# communication.net
KiCad netlist of a schematic drawn in Altium Designer
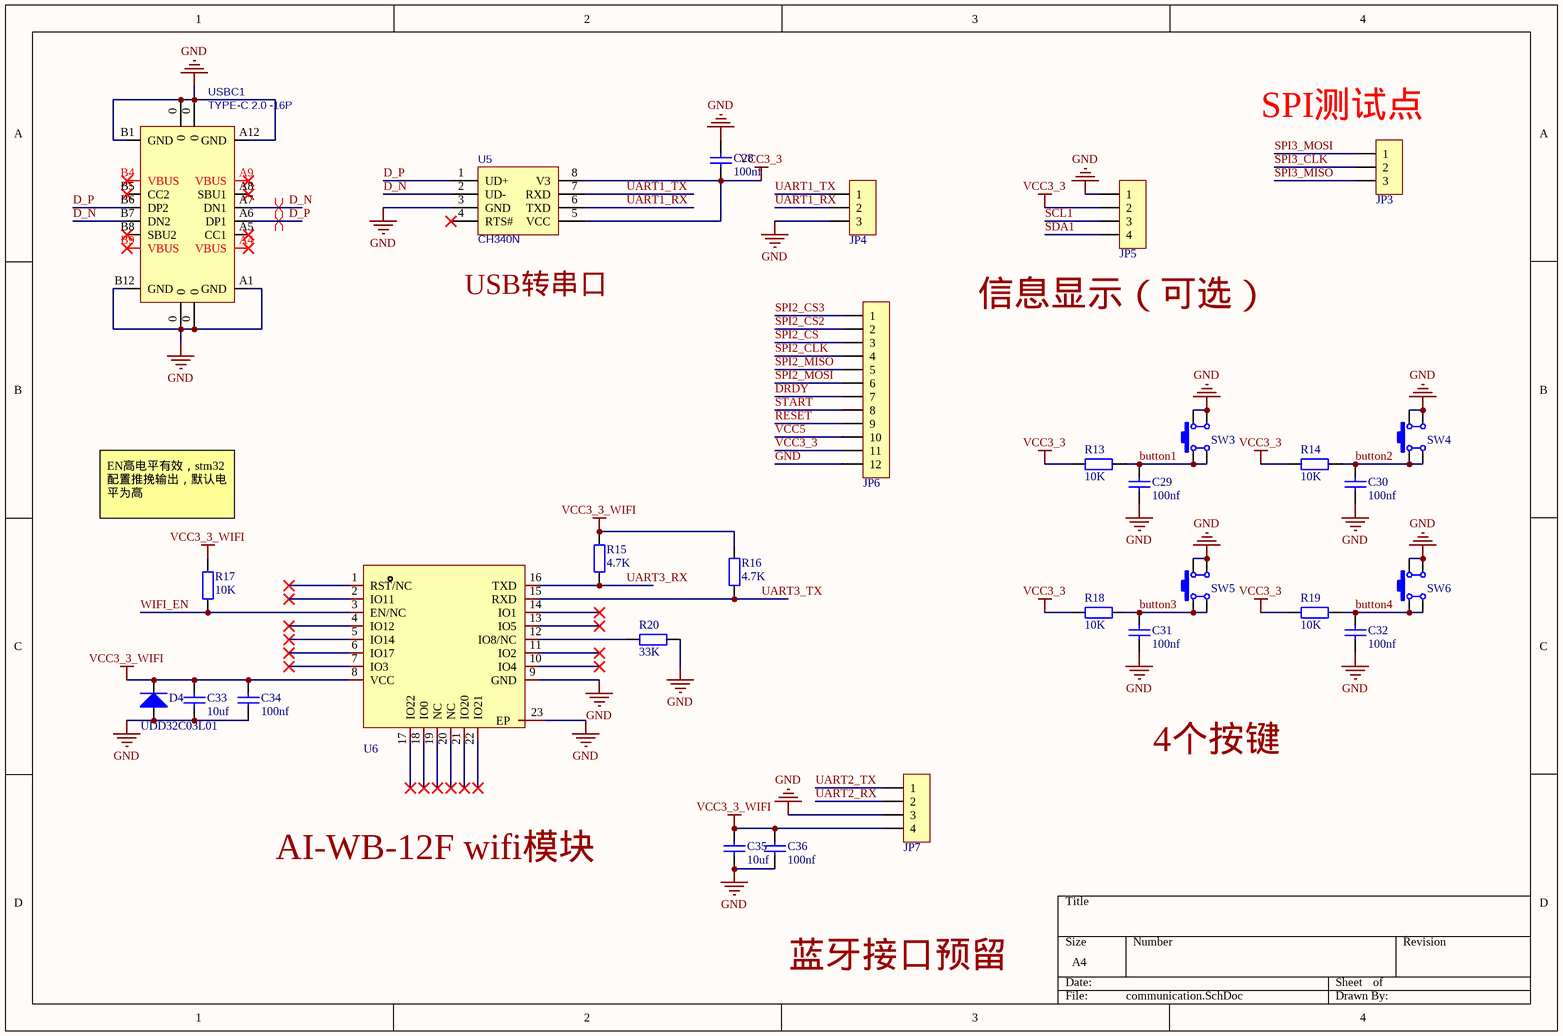
[diagram p0: communication.SchDoc]

(export (version "E")
  (design (tool "Eeschema 10.0.6"))
  (components
    (comp (ref "C28")
      (value "100nf")
      (footprint "C0603_L")
      (description "贴片电容/MLCC电容")
      (libsource (lib "0.1 - 电阻-电容-电感-保险丝-晶振-晶体-磁珠-电位器-法拉电容-馈通电容") (part "C"))
    )
    (comp (ref "C29")
      (value "100nf")
      (footprint "C0603_L")
      (description "贴片电容/MLCC电容")
      (libsource (lib "0.1 - 电阻-电容-电感-保险丝-晶振-晶体-磁珠-电位器-法拉电容-馈通电容") (part "C"))
    )
    (comp (ref "C30")
      (value "100nf")
      (footprint "C0603_L")
      (description "贴片电容/MLCC电容")
      (libsource (lib "0.1 - 电阻-电容-电感-保险丝-晶振-晶体-磁珠-电位器-法拉电容-馈通电容") (part "C"))
    )
    (comp (ref "C31")
      (value "100nf")
      (footprint "C0603_L")
      (description "贴片电容/MLCC电容")
      (libsource (lib "0.1 - 电阻-电容-电感-保险丝-晶振-晶体-磁珠-电位器-法拉电容-馈通电容") (part "C"))
    )
    (comp (ref "C32")
      (value "100nf")
      (footprint "C0603_L")
      (description "贴片电容/MLCC电容")
      (libsource (lib "0.1 - 电阻-电容-电感-保险丝-晶振-晶体-磁珠-电位器-法拉电容-馈通电容") (part "C"))
    )
    (comp (ref "C33")
      (value "10uf")
      (footprint "C0603_L")
      (description "贴片电容/MLCC电容")
      (libsource (lib "0.1 - 电阻-电容-电感-保险丝-晶振-晶体-磁珠-电位器-法拉电容-馈通电容") (part "C"))
    )
    (comp (ref "C34")
      (value "100nf")
      (footprint "C0603_L")
      (description "贴片电容/MLCC电容")
      (libsource (lib "0.1 - 电阻-电容-电感-保险丝-晶振-晶体-磁珠-电位器-法拉电容-馈通电容") (part "C"))
    )
    (comp (ref "C35")
      (value "10uf")
      (footprint "C0603_L")
      (description "贴片电容/MLCC电容")
      (libsource (lib "0.1 - 电阻-电容-电感-保险丝-晶振-晶体-磁珠-电位器-法拉电容-馈通电容") (part "C"))
    )
    (comp (ref "C36")
      (value "100nf")
      (footprint "C0603_L")
      (description "贴片电容/MLCC电容")
      (libsource (lib "0.1 - 电阻-电容-电感-保险丝-晶振-晶体-磁珠-电位器-法拉电容-馈通电容") (part "C"))
    )
    (comp (ref "D4")
      (value "UDD32C03L01")
      (footprint "SOD-323")
      (description "静电和浪涌保护 3.3V双向")
      (libsource (lib "HT") (part "UDD32C03L01"))
    )
    (comp (ref "JP3")
      (value "HDR-1X3")
      (footprint "HDR2.54-LI-3P")
      (description "3P接插件")
      (libsource (lib "5.5 - 2.54mm连接器(KF2EDGK_XH2.54_2.54排针排母)") (part "Header 3"))
    )
    (comp (ref "JP4")
      (value "HDR-1X3")
      (footprint "HDR2.54-LI-3P")
      (description "3P接插件")
      (libsource (lib "5.5 - 2.54mm连接器(KF2EDGK_XH2.54_2.54排针排母)") (part "Header 3"))
    )
    (comp (ref "JP5")
      (value "HDR-1X4")
      (footprint "HDR2.54-M-LI-4P")
      (description "4P接插件")
      (libsource (lib "5.5 - 2.54mm连接器(KF2EDGK_XH2.54_2.54排针排母)") (part "Header 4"))
    )
    (comp (ref "JP6")
      (value "HDR-1X12")
      (footprint "HDR2.54-M-LI-12P")
      (description "12P接插件")
      (libsource (lib "5.5 - 2.54mm连接器(KF2EDGK_XH2.54_2.54排针排母)") (part "Header 12"))
    )
    (comp (ref "JP7")
      (value "HDR-1X4")
      (footprint "HDR2.54-M-LI-4P")
      (description "4P接插件")
      (libsource (lib "5.5 - 2.54mm连接器(KF2EDGK_XH2.54_2.54排针排母)") (part "Header 4"))
    )
    (comp (ref "R13")
      (value "10K")
      (footprint "R0603_L")
      (description "贴片电阻")
      (libsource (lib "0.1 - 电阻-电容-电感-保险丝-晶振-晶体-磁珠-电位器-法拉电容-馈通电容") (part "R"))
    )
    (comp (ref "R14")
      (value "10K")
      (footprint "R0603_L")
      (description "贴片电阻")
      (libsource (lib "0.1 - 电阻-电容-电感-保险丝-晶振-晶体-磁珠-电位器-法拉电容-馈通电容") (part "R"))
    )
    (comp (ref "R15")
      (value "4.7K")
      (footprint "R0402_L")
      (description "贴片电阻")
      (libsource (lib "0.1 - 电阻-电容-电感-保险丝-晶振-晶体-磁珠-电位器-法拉电容-馈通电容") (part "R"))
    )
    (comp (ref "R16")
      (value "4.7K")
      (footprint "R0402_L")
      (description "贴片电阻")
      (libsource (lib "0.1 - 电阻-电容-电感-保险丝-晶振-晶体-磁珠-电位器-法拉电容-馈通电容") (part "R"))
    )
    (comp (ref "R17")
      (value "10K")
      (footprint "R0402_L")
      (description "贴片电阻")
      (libsource (lib "0.1 - 电阻-电容-电感-保险丝-晶振-晶体-磁珠-电位器-法拉电容-馈通电容") (part "R"))
    )
    (comp (ref "R18")
      (value "10K")
      (footprint "R0603_L")
      (description "贴片电阻")
      (libsource (lib "0.1 - 电阻-电容-电感-保险丝-晶振-晶体-磁珠-电位器-法拉电容-馈通电容") (part "R"))
    )
    (comp (ref "R19")
      (value "10K")
      (footprint "R0603_L")
      (description "贴片电阻")
      (libsource (lib "0.1 - 电阻-电容-电感-保险丝-晶振-晶体-磁珠-电位器-法拉电容-馈通电容") (part "R"))
    )
    (comp (ref "R20")
      (value "33K")
      (footprint "R0402_L")
      (description "贴片电阻")
      (libsource (lib "0.1 - 电阻-电容-电感-保险丝-晶振-晶体-磁珠-电位器-法拉电容-馈通电容") (part "R"))
    )
    (comp (ref "SW3")
      (value "3*4*2.5")
      (footprint "SW-SMD-4.2x3.2_4P")
      (description "贴片4脚轻触开关")
      (libsource (lib "0.5 - 按键_开关_蜂鸣器_电池_测试点_Mark点_铜柱") (part "SW SMD-3*4*2.5"))
    )
    (comp (ref "SW4")
      (value "3*4*2.5")
      (footprint "SW-SMD-4.2x3.2_4P")
      (description "贴片4脚轻触开关")
      (libsource (lib "0.5 - 按键_开关_蜂鸣器_电池_测试点_Mark点_铜柱") (part "SW SMD-3*4*2.5"))
    )
    (comp (ref "SW5")
      (value "3*4*2.5")
      (footprint "SW-SMD-4.2x3.2_4P")
      (description "贴片4脚轻触开关")
      (libsource (lib "0.5 - 按键_开关_蜂鸣器_电池_测试点_Mark点_铜柱") (part "SW SMD-3*4*2.5"))
    )
    (comp (ref "SW6")
      (value "3*4*2.5")
      (footprint "SW-SMD-4.2x3.2_4P")
      (description "贴片4脚轻触开关")
      (libsource (lib "0.5 - 按键_开关_蜂鸣器_电池_测试点_Mark点_铜柱") (part "SW SMD-3*4*2.5"))
    )
    (comp (ref "U5")
      (value "CH340N")
      (footprint "SOIC-8")
      (description "USB转串口芯片, 内置晶振")
      (libsource (lib "0.8 - 常见芯片") (part "CH340N"))
    )
    (comp (ref "U6")
      (value "Ai-WB2-12F")
      (footprint "ai-wb-12f")
      (description "esp32-12f的替代 2.4g wifi和蓝牙")
      (fields (field (name "MANUFACTURER") "Ai-Thinker(安信可)"))
      (libsource (lib "HT") (part "Ai-WB2-12F"))
    )
    (comp (ref "USBC1")
      (value "TYPE-C 2.0 -16P")
      (footprint "USB-C-SMD_16P")
      (description "USB2.0_Type-C_16Pin母座 C2765186")
      (libsource (lib "0.6 - 电源_音频_USB Type-C_HDMI_XT60_5557_D-SUB_RJ45_SD-TF_SIM插座") (part "USB2.0_Type-C_16Pin"))
    )
  )
  (nets
    (net (code "1") (name "/DRDY") (class "Default")
      (node (ref "JP6") (pin "7") (pinfunction "7_7") (pintype "passive"))
    )
    (net (code "2") (name "/D_N") (class "Default")
      (node (ref "U5") (pin "2") (pinfunction "UD-_2") (pintype "passive"))
      (node (ref "USBC1") (pin "A7") (pinfunction "DN1_A7") (pintype "passive"))
      (node (ref "USBC1") (pin "B7") (pinfunction "DN2_B7") (pintype "passive"))
    )
    (net (code "3") (name "/D_P") (class "Default")
      (node (ref "U5") (pin "1") (pinfunction "UD+_1") (pintype "passive"))
      (node (ref "USBC1") (pin "A6") (pinfunction "DP1_A6") (pintype "passive"))
      (node (ref "USBC1") (pin "B6") (pinfunction "DP2_B6") (pintype "passive"))
    )
    (net (code "4") (name "/RESET") (class "Default")
      (node (ref "JP6") (pin "9") (pinfunction "9_9") (pintype "passive"))
    )
    (net (code "5") (name "/SCL1") (class "Default")
      (node (ref "JP5") (pin "3") (pinfunction "3_3") (pintype "passive"))
    )
    (net (code "6") (name "/SDA1") (class "Default")
      (node (ref "JP5") (pin "4") (pinfunction "4_4") (pintype "passive"))
    )
    (net (code "7") (name "/SPI2_CLK") (class "Default")
      (node (ref "JP6") (pin "4") (pinfunction "4_4") (pintype "passive"))
    )
    (net (code "8") (name "/SPI2_CS") (class "Default")
      (node (ref "JP6") (pin "3") (pinfunction "3_3") (pintype "passive"))
    )
    (net (code "9") (name "/SPI2_CS2") (class "Default")
      (node (ref "JP6") (pin "2") (pinfunction "2_2") (pintype "passive"))
    )
    (net (code "10") (name "/SPI2_CS3") (class "Default")
      (node (ref "JP6") (pin "1") (pinfunction "1_1") (pintype "passive"))
    )
    (net (code "11") (name "/SPI2_MISO") (class "Default")
      (node (ref "JP6") (pin "5") (pinfunction "5_5") (pintype "passive"))
    )
    (net (code "12") (name "/SPI2_MOSI") (class "Default")
      (node (ref "JP6") (pin "6") (pinfunction "6_6") (pintype "passive"))
    )
    (net (code "13") (name "/SPI3_CLK") (class "Default")
      (node (ref "JP3") (pin "2") (pinfunction "2_2") (pintype "passive"))
    )
    (net (code "14") (name "/SPI3_MISO") (class "Default")
      (node (ref "JP3") (pin "3") (pinfunction "3_3") (pintype "passive"))
    )
    (net (code "15") (name "/SPI3_MOSI") (class "Default")
      (node (ref "JP3") (pin "1") (pinfunction "1_1") (pintype "passive"))
    )
    (net (code "16") (name "/START") (class "Default")
      (node (ref "JP6") (pin "8") (pinfunction "8_8") (pintype "passive"))
    )
    (net (code "17") (name "/UART1_RX") (class "Default")
      (node (ref "JP4") (pin "2") (pinfunction "2_2") (pintype "passive"))
      (node (ref "U5") (pin "6") (pinfunction "TXD_6") (pintype "passive"))
    )
    (net (code "18") (name "/UART1_TX") (class "Default")
      (node (ref "JP4") (pin "1") (pinfunction "1_1") (pintype "passive"))
      (node (ref "U5") (pin "7") (pinfunction "RXD_7") (pintype "passive"))
    )
    (net (code "19") (name "/UART2_RX") (class "Default")
      (node (ref "JP7") (pin "2") (pinfunction "2_2") (pintype "passive"))
    )
    (net (code "20") (name "/UART2_TX") (class "Default")
      (node (ref "JP7") (pin "1") (pinfunction "1_1") (pintype "passive"))
    )
    (net (code "21") (name "/UART3_RX") (class "Default")
      (node (ref "R15") (pin "2") (pinfunction "2_2") (pintype "passive"))
      (node (ref "U6") (pin "16") (pinfunction "TXD_16") (pintype "passive"))
    )
    (net (code "22") (name "/UART3_TX") (class "Default")
      (node (ref "R16") (pin "2") (pinfunction "2_2") (pintype "passive"))
      (node (ref "U6") (pin "15") (pinfunction "RXD_15") (pintype "passive"))
    )
    (net (code "23") (name "/VCC5") (class "Default")
      (node (ref "JP6") (pin "10") (pinfunction "10_10") (pintype "passive"))
    )
    (net (code "24") (name "/WIFI_EN") (class "Default")
      (node (ref "R17") (pin "1") (pinfunction "1_1") (pintype "passive"))
      (node (ref "U6") (pin "3") (pinfunction "EN/NC_3") (pintype "passive"))
    )
    (net (code "25") (name "/button1") (class "Default")
      (node (ref "C29") (pin "2") (pinfunction "2_2") (pintype "passive"))
      (node (ref "R13") (pin "2") (pinfunction "2_2") (pintype "passive"))
      (node (ref "SW3") (pin "1") (pinfunction "1_1") (pintype "passive"))
      (node (ref "SW3") (pin "4") (pinfunction "4_4") (pintype "passive"))
    )
    (net (code "26") (name "/button2") (class "Default")
      (node (ref "C30") (pin "2") (pinfunction "2_2") (pintype "passive"))
      (node (ref "R14") (pin "2") (pinfunction "2_2") (pintype "passive"))
      (node (ref "SW4") (pin "1") (pinfunction "1_1") (pintype "passive"))
      (node (ref "SW4") (pin "4") (pinfunction "4_4") (pintype "passive"))
    )
    (net (code "27") (name "/button3") (class "Default")
      (node (ref "C31") (pin "2") (pinfunction "2_2") (pintype "passive"))
      (node (ref "R18") (pin "2") (pinfunction "2_2") (pintype "passive"))
      (node (ref "SW5") (pin "1") (pinfunction "1_1") (pintype "passive"))
      (node (ref "SW5") (pin "4") (pinfunction "4_4") (pintype "passive"))
    )
    (net (code "28") (name "/button4") (class "Default")
      (node (ref "C32") (pin "2") (pinfunction "2_2") (pintype "passive"))
      (node (ref "R19") (pin "2") (pinfunction "2_2") (pintype "passive"))
      (node (ref "SW6") (pin "1") (pinfunction "1_1") (pintype "passive"))
      (node (ref "SW6") (pin "4") (pinfunction "4_4") (pintype "passive"))
    )
    (net (code "29") (name "GND") (class "Default")
      (node (ref "C28") (pin "2") (pinfunction "2_2") (pintype "passive"))
      (node (ref "C29") (pin "1") (pinfunction "1_1") (pintype "passive"))
      (node (ref "C30") (pin "1") (pinfunction "1_1") (pintype "passive"))
      (node (ref "C31") (pin "1") (pinfunction "1_1") (pintype "passive"))
      (node (ref "C32") (pin "1") (pinfunction "1_1") (pintype "passive"))
      (node (ref "C33") (pin "1") (pinfunction "1_1") (pintype "passive"))
      (node (ref "C34") (pin "1") (pinfunction "1_1") (pintype "passive"))
      (node (ref "C35") (pin "1") (pinfunction "1_1") (pintype "passive"))
      (node (ref "C36") (pin "1") (pinfunction "1_1") (pintype "passive"))
      (node (ref "D4") (pin "1") (pinfunction "A_1") (pintype "passive"))
      (node (ref "JP4") (pin "3") (pinfunction "3_3") (pintype "passive"))
      (node (ref "JP5") (pin "1") (pinfunction "1_1") (pintype "passive"))
      (node (ref "JP6") (pin "12") (pinfunction "12_12") (pintype "passive"))
      (node (ref "JP7") (pin "3") (pinfunction "3_3") (pintype "passive"))
      (node (ref "R20") (pin "1") (pinfunction "1_1") (pintype "passive"))
      (node (ref "SW3") (pin "2") (pinfunction "2_2") (pintype "passive"))
      (node (ref "SW3") (pin "3") (pinfunction "3_3") (pintype "passive"))
      (node (ref "SW4") (pin "2") (pinfunction "2_2") (pintype "passive"))
      (node (ref "SW4") (pin "3") (pinfunction "3_3") (pintype "passive"))
      (node (ref "SW5") (pin "2") (pinfunction "2_2") (pintype "passive"))
      (node (ref "SW5") (pin "3") (pinfunction "3_3") (pintype "passive"))
      (node (ref "SW6") (pin "2") (pinfunction "2_2") (pintype "passive"))
      (node (ref "SW6") (pin "3") (pinfunction "3_3") (pintype "passive"))
      (node (ref "U5") (pin "3") (pinfunction "GND_3") (pintype "passive"))
      (node (ref "U6") (pin "23") (pinfunction "EP_23") (pintype "passive"))
      (node (ref "U6") (pin "9") (pinfunction "GND_9") (pintype "passive"))
      (node (ref "USBC1") (pin "0") (pinfunction "0_0") (pintype "passive"))
      (node (ref "USBC1") (pin "A1") (pinfunction "GND_A1") (pintype "passive"))
      (node (ref "USBC1") (pin "A12") (pinfunction "GND_A12") (pintype "passive"))
      (node (ref "USBC1") (pin "B1") (pinfunction "GND_B1") (pintype "passive"))
      (node (ref "USBC1") (pin "B12") (pinfunction "GND_B12") (pintype "passive"))
    )
    (net (code "30") (name "Net-(U6-IO8{slash}NC)") (class "Default")
      (node (ref "R20") (pin "2") (pinfunction "2_2") (pintype "passive"))
      (node (ref "U6") (pin "12") (pinfunction "IO8/NC_12") (pintype "passive"))
    )
    (net (code "31") (name "VCC3_3") (class "Default")
      (node (ref "C28") (pin "1") (pinfunction "1_1") (pintype "passive"))
      (node (ref "JP5") (pin "2") (pinfunction "2_2") (pintype "passive"))
      (node (ref "JP6") (pin "11") (pinfunction "11_11") (pintype "passive"))
      (node (ref "R13") (pin "1") (pinfunction "1_1") (pintype "passive"))
      (node (ref "R14") (pin "1") (pinfunction "1_1") (pintype "passive"))
      (node (ref "R18") (pin "1") (pinfunction "1_1") (pintype "passive"))
      (node (ref "R19") (pin "1") (pinfunction "1_1") (pintype "passive"))
      (node (ref "U5") (pin "5") (pinfunction "VCC_5") (pintype "passive"))
      (node (ref "U5") (pin "8") (pinfunction "V3_8") (pintype "passive"))
    )
    (net (code "32") (name "VCC3_3_WIFI") (class "Default")
      (node (ref "C33") (pin "2") (pinfunction "2_2") (pintype "passive"))
      (node (ref "C34") (pin "2") (pinfunction "2_2") (pintype "passive"))
      (node (ref "C35") (pin "2") (pinfunction "2_2") (pintype "passive"))
      (node (ref "C36") (pin "2") (pinfunction "2_2") (pintype "passive"))
      (node (ref "D4") (pin "2") (pinfunction "K_2") (pintype "passive"))
      (node (ref "JP7") (pin "4") (pinfunction "4_4") (pintype "passive"))
      (node (ref "R15") (pin "1") (pinfunction "1_1") (pintype "passive"))
      (node (ref "R16") (pin "1") (pinfunction "1_1") (pintype "passive"))
      (node (ref "R17") (pin "2") (pinfunction "2_2") (pintype "passive"))
      (node (ref "U6") (pin "8") (pinfunction "VCC_8") (pintype "passive"))
    )
    (net (code "33") (name "unconnected-(U5-RTS#-Pad4)") (class "Default")
      (node (ref "U5") (pin "4") (pinfunction "RTS#_4") (pintype "passive+no_connect"))
    )
    (net (code "34") (name "unconnected-(U6-IO0-Pad18)") (class "Default")
      (node (ref "U6") (pin "18") (pinfunction "IO0_18") (pintype "passive+no_connect"))
    )
    (net (code "35") (name "unconnected-(U6-IO1-Pad14)") (class "Default")
      (node (ref "U6") (pin "14") (pinfunction "IO1_14") (pintype "passive+no_connect"))
    )
    (net (code "36") (name "unconnected-(U6-IO2-Pad11)") (class "Default")
      (node (ref "U6") (pin "11") (pinfunction "IO2_11") (pintype "passive+no_connect"))
    )
    (net (code "37") (name "unconnected-(U6-IO3-Pad7)") (class "Default")
      (node (ref "U6") (pin "7") (pinfunction "IO3_7") (pintype "passive+no_connect"))
    )
    (net (code "38") (name "unconnected-(U6-IO4-Pad10)") (class "Default")
      (node (ref "U6") (pin "10") (pinfunction "IO4_10") (pintype "passive+no_connect"))
    )
    (net (code "39") (name "unconnected-(U6-IO5-Pad13)") (class "Default")
      (node (ref "U6") (pin "13") (pinfunction "IO5_13") (pintype "passive+no_connect"))
    )
    (net (code "40") (name "unconnected-(U6-IO11-Pad2)") (class "Default")
      (node (ref "U6") (pin "2") (pinfunction "IO11_2") (pintype "passive+no_connect"))
    )
    (net (code "41") (name "unconnected-(U6-IO12-Pad4)") (class "Default")
      (node (ref "U6") (pin "4") (pinfunction "IO12_4") (pintype "passive+no_connect"))
    )
    (net (code "42") (name "unconnected-(U6-IO14-Pad5)") (class "Default")
      (node (ref "U6") (pin "5") (pinfunction "IO14_5") (pintype "passive+no_connect"))
    )
    (net (code "43") (name "unconnected-(U6-IO17-Pad6)") (class "Default")
      (node (ref "U6") (pin "6") (pinfunction "IO17_6") (pintype "passive+no_connect"))
    )
    (net (code "44") (name "unconnected-(U6-IO20-Pad21)") (class "Default")
      (node (ref "U6") (pin "21") (pinfunction "IO20_21") (pintype "passive+no_connect"))
    )
    (net (code "45") (name "unconnected-(U6-IO21-Pad22)") (class "Default")
      (node (ref "U6") (pin "22") (pinfunction "IO21_22") (pintype "passive+no_connect"))
    )
    (net (code "46") (name "unconnected-(U6-IO22-Pad17)") (class "Default")
      (node (ref "U6") (pin "17") (pinfunction "IO22_17") (pintype "passive+no_connect"))
    )
    (net (code "47") (name "unconnected-(U6-NC-Pad19)") (class "Default")
      (node (ref "U6") (pin "19") (pinfunction "NC_19") (pintype "passive+no_connect"))
    )
    (net (code "48") (name "unconnected-(U6-NC-Pad20)") (class "Default")
      (node (ref "U6") (pin "20") (pinfunction "NC_20") (pintype "passive+no_connect"))
    )
    (net (code "49") (name "unconnected-(U6-RST{slash}NC-Pad1)") (class "Default")
      (node (ref "U6") (pin "1") (pinfunction "RST/NC_1") (pintype "passive+no_connect"))
    )
    (net (code "50") (name "unconnected-(USBC1-CC1-PadA5)") (class "Default")
      (node (ref "USBC1") (pin "A5") (pinfunction "CC1_A5") (pintype "passive+no_connect"))
    )
    (net (code "51") (name "unconnected-(USBC1-CC2-PadB5)") (class "Default")
      (node (ref "USBC1") (pin "B5") (pinfunction "CC2_B5") (pintype "passive+no_connect"))
    )
    (net (code "52") (name "unconnected-(USBC1-SBU1-PadA8)") (class "Default")
      (node (ref "USBC1") (pin "A8") (pinfunction "SBU1_A8") (pintype "passive+no_connect"))
    )
    (net (code "53") (name "unconnected-(USBC1-SBU2-PadB8)") (class "Default")
      (node (ref "USBC1") (pin "B8") (pinfunction "SBU2_B8") (pintype "passive+no_connect"))
    )
    (net (code "54") (name "unconnected-(USBC1-VBUS-PadA4)") (class "Default")
      (node (ref "USBC1") (pin "A4") (pinfunction "VBUS_A4") (pintype "passive+no_connect"))
    )
    (net (code "55") (name "unconnected-(USBC1-VBUS-PadA9)") (class "Default")
      (node (ref "USBC1") (pin "A9") (pinfunction "VBUS_A9") (pintype "passive+no_connect"))
    )
    (net (code "56") (name "unconnected-(USBC1-VBUS-PadB4)") (class "Default")
      (node (ref "USBC1") (pin "B4") (pinfunction "VBUS_B4") (pintype "passive+no_connect"))
    )
    (net (code "57") (name "unconnected-(USBC1-VBUS-PadB9)") (class "Default")
      (node (ref "USBC1") (pin "B9") (pinfunction "VBUS_B9") (pintype "passive+no_connect"))
    )
  )
)
